# ersa_schematics_digital.net
KiCad netlist of a schematic drawn in Altium Designer
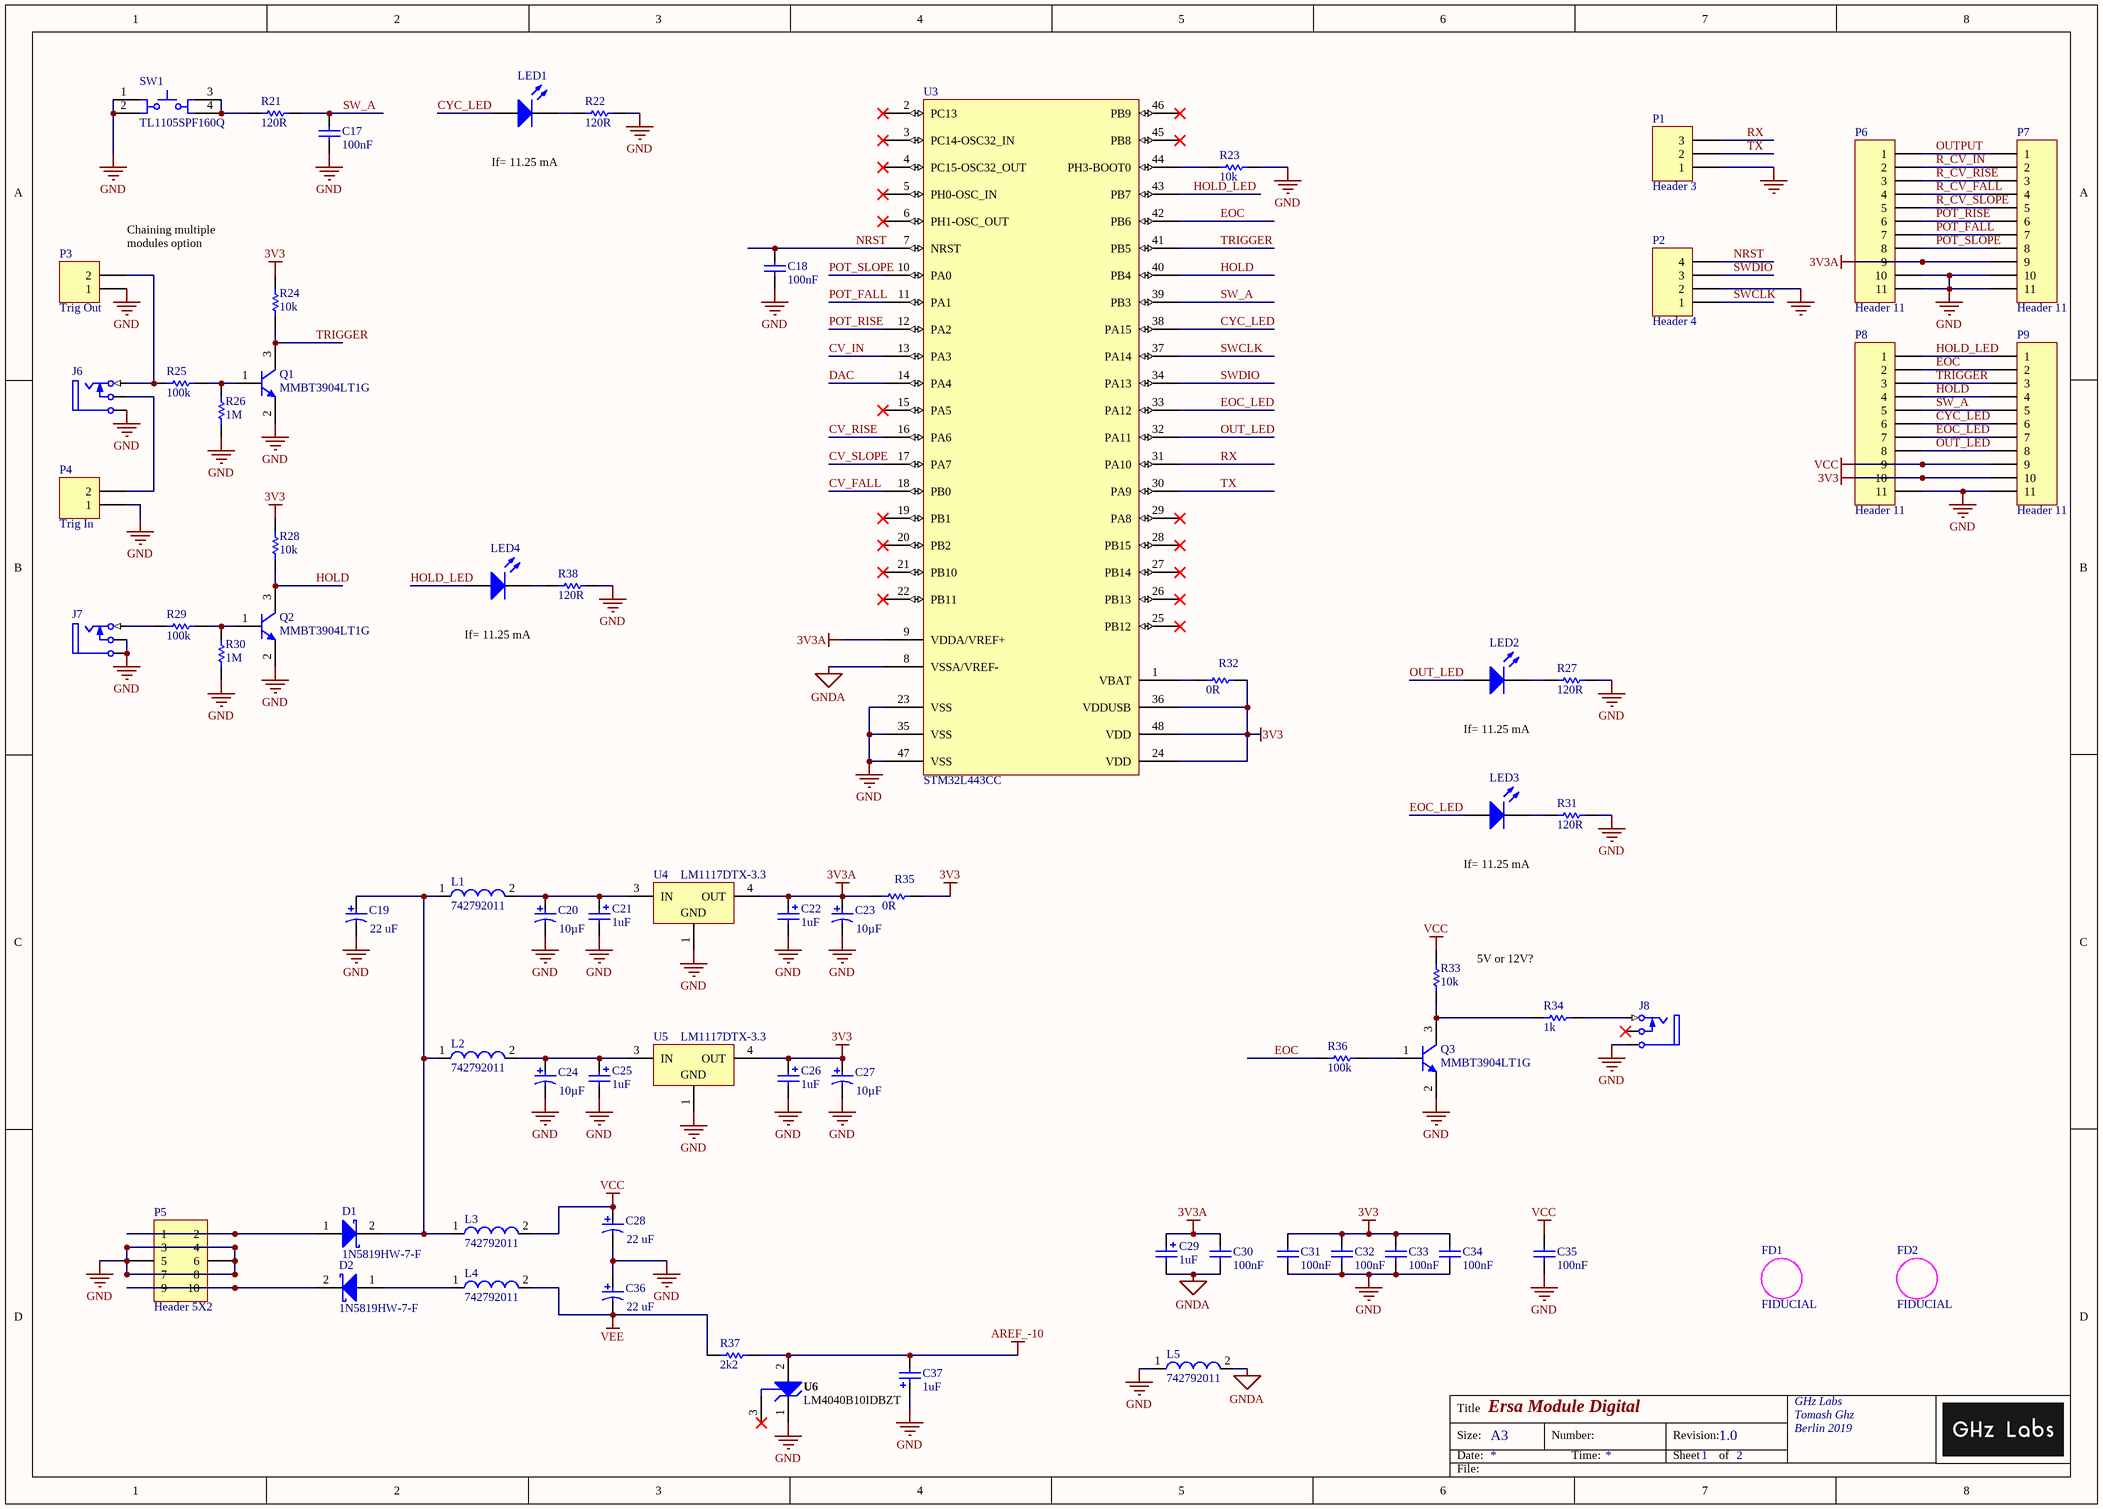
[diagram p0: ersa_schematics_digital.SchDoc]

(export (version "E")
  (design (tool "Eeschema 10.0.6"))
  (components
    (comp (ref "C17")
      (value "100nF")
      (footprint "GHzLabs_Parts:CAPA_0805")
      (description "Capacitor")
      (fields (field (name "PUBLISHER") "Altium Limited"))
      (libsource (lib "Miscellaneous Devices") (part "Cap"))
    )
    (comp (ref "C18")
      (value "100nF")
      (footprint "GHzLabs_Parts:CAPA_0805")
      (description "Capacitor")
      (fields (field (name "PUBLISHER") "Altium Limited"))
      (libsource (lib "Miscellaneous Devices") (part "Cap"))
    )
    (comp (ref "C19")
      (value "UUD1C220MCL1GS")
      (footprint "NIC-CAPA2-5X5.8_V")
      (fields (field (name "RATED CAPACITANCE") "22 uF") (field (name "MANUFACTURER") "Nichicon"))
      (libsource (lib "Altium Content Vault") (part "CMP-0687-00027-1"))
    )
    (comp (ref "C20")
      (value "EEE-FK1V100UR")
      (footprint "PNSC-FK-V-B_V")
      (fields (field (name "MANUFACTURER") "Panasonic") (field (name "CAPACITANCE") "10µF"))
      (libsource (lib "Altium Content Vault") (part "CMP-2000-06211-1"))
    )
    (comp (ref "C21")
      (value "1uF")
      (footprint "GHzLabs_Parts:CAPA_0805 Pol")
      (description "Polarized Capacitor")
      (fields
        (field (name "PARTNUMBER") "GRM21BR61C105KA01L")
        (field (name "MANUFACTURER") "Murata Electronics")
      )
      (libsource (lib "Miscellaneous Devices") (part "Cap Pol2"))
    )
    (comp (ref "C22")
      (value "1uF")
      (footprint "GHzLabs_Parts:CAPA_0805 Pol")
      (description "Polarized Capacitor")
      (fields
        (field (name "PARTNUMBER") "GRM21BR61C105KA01L")
        (field (name "MANUFACTURER") "Murata Electronics")
      )
      (libsource (lib "Miscellaneous Devices") (part "Cap Pol2"))
    )
    (comp (ref "C23")
      (value "EEE-FK1V100UR")
      (footprint "PNSC-FK-V-B_V")
      (fields (field (name "MANUFACTURER") "Panasonic") (field (name "CAPACITANCE") "10µF"))
      (libsource (lib "Altium Content Vault") (part "CMP-2000-06211-1"))
    )
    (comp (ref "C24")
      (value "EEE-FK1V100UR")
      (footprint "PNSC-FK-V-B_V")
      (fields (field (name "MANUFACTURER") "Panasonic") (field (name "CAPACITANCE") "10µF"))
      (libsource (lib "Altium Content Vault") (part "CMP-2000-06211-1"))
    )
    (comp (ref "C25")
      (value "1uF")
      (footprint "GHzLabs_Parts:CAPA_0805 Pol")
      (description "Polarized Capacitor")
      (fields
        (field (name "PARTNUMBER") "GRM21BR61C105KA01L")
        (field (name "MANUFACTURER") "Murata Electronics")
      )
      (libsource (lib "Miscellaneous Devices") (part "Cap Pol2"))
    )
    (comp (ref "C26")
      (value "1uF")
      (footprint "GHzLabs_Parts:CAPA_0805 Pol")
      (description "Polarized Capacitor")
      (fields
        (field (name "PARTNUMBER") "GRM21BR61C105KA01L")
        (field (name "MANUFACTURER") "Murata Electronics")
      )
      (libsource (lib "Miscellaneous Devices") (part "Cap Pol2"))
    )
    (comp (ref "C27")
      (value "EEE-FK1V100UR")
      (footprint "PNSC-FK-V-B_V")
      (fields (field (name "MANUFACTURER") "Panasonic") (field (name "CAPACITANCE") "10µF"))
      (libsource (lib "Altium Content Vault") (part "CMP-2000-06211-1"))
    )
    (comp (ref "C28")
      (value "UUD1C220MCL1GS")
      (footprint "NIC-CAPA2-5X5.8_V")
      (fields (field (name "RATED CAPACITANCE") "22 uF") (field (name "MANUFACTURER") "Nichicon"))
      (libsource (lib "Altium Content Vault") (part "CMP-0687-00027-1"))
    )
    (comp (ref "C29")
      (value "1uF")
      (footprint "GHzLabs_Parts:CAPA_0805 Pol")
      (description "Polarized Capacitor")
      (fields
        (field (name "PARTNUMBER") "GRM21BR61C105KA01L")
        (field (name "MANUFACTURER") "Murata Electronics")
      )
      (libsource (lib "Miscellaneous Devices") (part "Cap Pol2"))
    )
    (comp (ref "C30")
      (value "100nF")
      (footprint "GHzLabs_Parts:CAPA_0805")
      (description "Capacitor")
      (fields (field (name "PUBLISHER") "Altium Limited"))
      (libsource (lib "Miscellaneous Devices") (part "Cap"))
    )
    (comp (ref "C31")
      (value "100nF")
      (footprint "GHzLabs_Parts:CAPA_0805")
      (description "Capacitor")
      (fields (field (name "PUBLISHER") "Altium Limited"))
      (libsource (lib "Miscellaneous Devices") (part "Cap"))
    )
    (comp (ref "C32")
      (value "100nF")
      (footprint "GHzLabs_Parts:CAPA_0805")
      (description "Capacitor")
      (fields (field (name "PUBLISHER") "Altium Limited"))
      (libsource (lib "Miscellaneous Devices") (part "Cap"))
    )
    (comp (ref "C33")
      (value "100nF")
      (footprint "GHzLabs_Parts:CAPA_0805")
      (description "Capacitor")
      (fields (field (name "PUBLISHER") "Altium Limited"))
      (libsource (lib "Miscellaneous Devices") (part "Cap"))
    )
    (comp (ref "C34")
      (value "100nF")
      (footprint "GHzLabs_Parts:CAPA_0805")
      (description "Capacitor")
      (fields (field (name "PUBLISHER") "Altium Limited"))
      (libsource (lib "Miscellaneous Devices") (part "Cap"))
    )
    (comp (ref "C35")
      (value "100nF")
      (footprint "GHzLabs_Parts:CAPA_0805")
      (description "Capacitor")
      (fields (field (name "PUBLISHER") "Altium Limited"))
      (libsource (lib "Miscellaneous Devices") (part "Cap"))
    )
    (comp (ref "C36")
      (value "UUD1C220MCL1GS")
      (footprint "NIC-CAPA2-5X5.8_V")
      (fields (field (name "RATED CAPACITANCE") "22 uF") (field (name "MANUFACTURER") "Nichicon"))
      (libsource (lib "Altium Content Vault") (part "CMP-0687-00027-1"))
    )
    (comp (ref "C37")
      (value "1uF")
      (footprint "GHzLabs_Parts:CAPA_0805 Pol")
      (description "Polarized Capacitor")
      (fields
        (field (name "PARTNUMBER") "GRM21BR61C105KA01L")
        (field (name "MANUFACTURER") "Murata Electronics")
      )
      (libsource (lib "Miscellaneous Devices") (part "Cap Pol2"))
    )
    (comp (ref "D1")
      (value "1N5819HW-7-F")
      (footprint "DIOD-SOD-123-2_V")
      (fields (field (name "MANUFACTURER") "Diodes Inc"))
      (libsource (lib "Altium Content Vault") (part "DIOD-DSKY-A1K2-2"))
    )
    (comp (ref "D2")
      (value "1N5819HW-7-F")
      (footprint "DIOD-SOD-123-2_V")
      (fields (field (name "MANUFACTURER") "Diodes Inc"))
      (libsource (lib "Altium Content Vault") (part "DIOD-DSKY-A1K2-2"))
    )
    (comp (ref "FD1")
      (value "FIDUCIAL")
      (footprint "GHzLabs_Parts:FIDUCIAL")
      (description "Fiducial - Round 1.5 mm Top-Bottom")
      (fields (field (name "MANUFACTURER") "No Vendor"))
      (libsource (lib "GHzLabs_Parts") (part "FIDUCIAL_ROUND"))
    )
    (comp (ref "FD2")
      (value "FIDUCIAL")
      (footprint "GHzLabs_Parts:FIDUCIAL")
      (description "Fiducial - Round 1.5 mm Top-Bottom")
      (fields (field (name "MANUFACTURER") "No Vendor"))
      (libsource (lib "GHzLabs_Parts") (part "FIDUCIAL_ROUND"))
    )
    (comp (ref "J6")
      (value "Phonejack2 TN")
      (footprint "GHzLabs_Parts:Thonkiconn")
      (description "Jack Socket")
      (fields (field (name "PART") "ACJM-MV35-2S") (field (name "MANUFACTURER") "Amphenol Audio"))
      (libsource (lib "GHzLabs_Parts") (part "Phonejack2 TN"))
    )
    (comp (ref "J7")
      (value "Phonejack2 TN")
      (footprint "GHzLabs_Parts:Thonkiconn")
      (description "Jack Socket")
      (fields (field (name "PART") "ACJM-MV35-2S") (field (name "MANUFACTURER") "Amphenol Audio"))
      (libsource (lib "GHzLabs_Parts") (part "Phonejack2 TN"))
    )
    (comp (ref "J8")
      (value "Phonejack2 TN")
      (footprint "GHzLabs_Parts:Thonkiconn")
      (description "Jack Socket")
      (fields (field (name "PART") "ACJM-MV35-2S") (field (name "MANUFACTURER") "Amphenol Audio"))
      (libsource (lib "GHzLabs_Parts") (part "Phonejack2 TN"))
    )
    (comp (ref "L1")
      (value "742792011")
      (footprint "SMD-0805")
      (description "SMD EMI Suppression Ferrite Bead WE-CBF, Z = 10 Ohm")
      (libsource (lib "Altium Content Vault") (part "PAS-IND-INDUCTOR-2"))
    )
    (comp (ref "L2")
      (value "742792011")
      (footprint "SMD-0805")
      (description "SMD EMI Suppression Ferrite Bead WE-CBF, Z = 10 Ohm")
      (libsource (lib "Altium Content Vault") (part "PAS-IND-INDUCTOR-2"))
    )
    (comp (ref "L3")
      (value "742792011")
      (footprint "SMD-0805")
      (description "SMD EMI Suppression Ferrite Bead WE-CBF, Z = 10 Ohm")
      (libsource (lib "Altium Content Vault") (part "PAS-IND-INDUCTOR-2"))
    )
    (comp (ref "L4")
      (value "742792011")
      (footprint "SMD-0805")
      (description "SMD EMI Suppression Ferrite Bead WE-CBF, Z = 10 Ohm")
      (libsource (lib "Altium Content Vault") (part "PAS-IND-INDUCTOR-2"))
    )
    (comp (ref "L5")
      (value "742792011")
      (footprint "SMD-0805")
      (description "SMD EMI Suppression Ferrite Bead WE-CBF, Z = 10 Ohm")
      (libsource (lib "Altium Content Vault") (part "PAS-IND-INDUCTOR-2"))
    )
    (comp (ref "LED1")
      (value "WP424YDT")
      (footprint "Type 3mm")
      (description "THT LED round mono-color color lens, WL-TMRC, Bright Green")
      (fields (field (name "MANUFACTURER") "Kingbright"))
      (libsource (lib "Altium Content Vault") (part "CMP-1488-00001-1"))
    )
    (comp (ref "LED2")
      (value "WP424YDT")
      (footprint "Type 3mm")
      (description "THT LED round mono-color color lens, WL-TMRC, Bright Green")
      (fields (field (name "MANUFACTURER") "Kingbright"))
      (libsource (lib "Altium Content Vault") (part "CMP-1488-00001-1"))
    )
    (comp (ref "LED3")
      (value "WP424YDT")
      (footprint "Type 3mm")
      (description "THT LED round mono-color color lens, WL-TMRC, Bright Green")
      (fields (field (name "MANUFACTURER") "Kingbright"))
      (libsource (lib "Altium Content Vault") (part "CMP-1488-00001-1"))
    )
    (comp (ref "LED4")
      (value "WP424YDT")
      (footprint "Type 3mm")
      (description "THT LED round mono-color color lens, WL-TMRC, Bright Green")
      (fields (field (name "MANUFACTURER") "Kingbright"))
      (libsource (lib "Altium Content Vault") (part "CMP-1488-00001-1"))
    )
    (comp (ref "P1")
      (value "Header 3")
      (footprint "HDR1X3")
      (description "Header, 3-Pin")
      (fields (field (name "PUBLISHER") "Altium Limited"))
      (libsource (lib "Miscellaneous Connectors") (part "Header 3"))
    )
    (comp (ref "P2")
      (value "Header 4")
      (footprint "HDR1X4")
      (description "Header, 4-Pin")
      (fields (field (name "PUBLISHER") "Altium Limited"))
      (libsource (lib "Miscellaneous Connectors") (part "Header 4"))
    )
    (comp (ref "P3")
      (value "Trig Out")
      (footprint "HDR1X2")
      (description "Header, 2-Pin")
      (fields (field (name "PUBLISHER") "Altium Limited"))
      (libsource (lib "Miscellaneous Connectors") (part "Header 2"))
    )
    (comp (ref "P4")
      (value "Trig In")
      (footprint "HDR1X2")
      (description "Header, 2-Pin")
      (fields (field (name "PUBLISHER") "Altium Limited"))
      (libsource (lib "Miscellaneous Connectors") (part "Header 2"))
    )
    (comp (ref "P5")
      (value "Header 5X2")
      (footprint "HDR2X5")
      (description "Header, 5-Pin, Dual row")
      (fields (field (name "PUBLISHER") "Altium Limited"))
      (libsource (lib "Miscellaneous Connectors") (part "Header 5X2"))
    )
    (comp (ref "P6")
      (value "Header 11")
      (footprint "HDR1X11")
      (description "Header, 11-Pin")
      (fields (field (name "PUBLISHER") "Altium Limited"))
      (libsource (lib "Miscellaneous Connectors") (part "Header 11"))
    )
    (comp (ref "P7")
      (value "Header 11")
      (footprint "HDR1X11")
      (description "Header, 11-Pin")
      (fields (field (name "PUBLISHER") "Altium Limited"))
      (libsource (lib "") (part "Header 11_1"))
    )
    (comp (ref "P8")
      (value "Header 11")
      (footprint "HDR1X11")
      (description "Header, 11-Pin")
      (fields (field (name "PUBLISHER") "Altium Limited"))
      (libsource (lib "Miscellaneous Connectors") (part "Header 11"))
    )
    (comp (ref "P9")
      (value "Header 11")
      (footprint "HDR1X11")
      (description "Header, 11-Pin")
      (fields (field (name "PUBLISHER") "Altium Limited"))
      (libsource (lib "") (part "Header 11_1"))
    )
    (comp (ref "Q1")
      (value "MMBT3904LT1G")
      (footprint "ONSC-SOT-23-3-318-08_V")
      (description "General Purpose Transistor, NPN Silicon, 3-Pin SOT-23, Pb-Free, Tape and Reel")
      (fields (field (name "MANUFACTURER") "On Semiconductor"))
      (libsource (lib "Altium Content Vault") (part "ONSC-NPN-B1E2C3-3"))
    )
    (comp (ref "Q2")
      (value "MMBT3904LT1G")
      (footprint "ONSC-SOT-23-3-318-08_V")
      (description "General Purpose Transistor, NPN Silicon, 3-Pin SOT-23, Pb-Free, Tape and Reel")
      (fields (field (name "MANUFACTURER") "On Semiconductor"))
      (libsource (lib "Altium Content Vault") (part "ONSC-NPN-B1E2C3-3"))
    )
    (comp (ref "Q3")
      (value "MMBT3904LT1G")
      (footprint "ONSC-SOT-23-3-318-08_V")
      (description "General Purpose Transistor, NPN Silicon, 3-Pin SOT-23, Pb-Free, Tape and Reel")
      (fields (field (name "MANUFACTURER") "On Semiconductor"))
      (libsource (lib "Altium Content Vault") (part "ONSC-NPN-B1E2C3-3"))
    )
    (comp (ref "R21")
      (value "120R")
      (footprint "GHzLabs_Parts:RES_0805")
      (description "120R 0805")
      (fields (field (name "PARTNUMBER") "RR1220P-105-D") (field (name "MANUFACTURER") "Susumu"))
      (libsource (lib "GHzLabs_Parts") (part "Resistor"))
    )
    (comp (ref "R22")
      (value "120R")
      (footprint "GHzLabs_Parts:RES_0805")
      (description "120R 0805")
      (fields (field (name "PARTNUMBER") "RR1220P-105-D") (field (name "MANUFACTURER") "Susumu"))
      (libsource (lib "GHzLabs_Parts") (part "Resistor"))
    )
    (comp (ref "R23")
      (value "10k")
      (footprint "GHzLabs_Parts:RES_0805")
      (description "10k 0805")
      (fields (field (name "PARTNUMBER") "RR1220P-105-D") (field (name "MANUFACTURER") "Susumu"))
      (libsource (lib "GHzLabs_Parts") (part "Resistor"))
    )
    (comp (ref "R24")
      (value "10k")
      (footprint "GHzLabs_Parts:RES_0805")
      (description "10k 0805")
      (fields (field (name "PARTNUMBER") "RR1220P-105-D") (field (name "MANUFACTURER") "Susumu"))
      (libsource (lib "GHzLabs_Parts") (part "Resistor"))
    )
    (comp (ref "R25")
      (value "100k")
      (footprint "GHzLabs_Parts:RES_0805")
      (description "100k 0805")
      (fields (field (name "PARTNUMBER") "RR1220P-105-D") (field (name "MANUFACTURER") "Susumu"))
      (libsource (lib "GHzLabs_Parts") (part "Resistor"))
    )
    (comp (ref "R26")
      (value "1M")
      (footprint "GHzLabs_Parts:RES_0805")
      (description "1M 0805")
      (fields (field (name "PARTNUMBER") "RR1220P-105-D") (field (name "MANUFACTURER") "Susumu"))
      (libsource (lib "GHzLabs_Parts") (part "Resistor"))
    )
    (comp (ref "R27")
      (value "120R")
      (footprint "GHzLabs_Parts:RES_0805")
      (description "120R 0805")
      (fields (field (name "PARTNUMBER") "RR1220P-105-D") (field (name "MANUFACTURER") "Susumu"))
      (libsource (lib "GHzLabs_Parts") (part "Resistor"))
    )
    (comp (ref "R28")
      (value "10k")
      (footprint "GHzLabs_Parts:RES_0805")
      (description "10k 0805")
      (fields (field (name "PARTNUMBER") "RR1220P-105-D") (field (name "MANUFACTURER") "Susumu"))
      (libsource (lib "GHzLabs_Parts") (part "Resistor"))
    )
    (comp (ref "R29")
      (value "100k")
      (footprint "GHzLabs_Parts:RES_0805")
      (description "100k 0805")
      (fields (field (name "PARTNUMBER") "RR1220P-105-D") (field (name "MANUFACTURER") "Susumu"))
      (libsource (lib "GHzLabs_Parts") (part "Resistor"))
    )
    (comp (ref "R30")
      (value "1M")
      (footprint "GHzLabs_Parts:RES_0805")
      (description "1M 0805")
      (fields (field (name "PARTNUMBER") "RR1220P-105-D") (field (name "MANUFACTURER") "Susumu"))
      (libsource (lib "GHzLabs_Parts") (part "Resistor"))
    )
    (comp (ref "R31")
      (value "120R")
      (footprint "GHzLabs_Parts:RES_0805")
      (description "120R 0805")
      (fields (field (name "PARTNUMBER") "RR1220P-105-D") (field (name "MANUFACTURER") "Susumu"))
      (libsource (lib "GHzLabs_Parts") (part "Resistor"))
    )
    (comp (ref "R32")
      (value "0R")
      (footprint "GHzLabs_Parts:RES_0805")
      (description "0R 0805")
      (fields (field (name "PARTNUMBER") "RR1220P-104-D") (field (name "MANUFACTURER") "Susumu"))
      (libsource (lib "myParts") (part "Resistor"))
    )
    (comp (ref "R33")
      (value "10k")
      (footprint "GHzLabs_Parts:RES_0805")
      (description "10k 0805")
      (fields (field (name "PARTNUMBER") "RR1220P-105-D") (field (name "MANUFACTURER") "Susumu"))
      (libsource (lib "GHzLabs_Parts") (part "Resistor"))
    )
    (comp (ref "R34")
      (value "1k")
      (footprint "GHzLabs_Parts:RES_0805")
      (description "1k 0805")
      (fields (field (name "PARTNUMBER") "RR1220P-105-D") (field (name "MANUFACTURER") "Susumu"))
      (libsource (lib "GHzLabs_Parts") (part "Resistor"))
    )
    (comp (ref "R35")
      (value "0R")
      (footprint "GHzLabs_Parts:RES_0805")
      (description "0R 0805")
      (fields (field (name "PARTNUMBER") "RR1220P-104-D") (field (name "MANUFACTURER") "Susumu"))
      (libsource (lib "myParts") (part "Resistor"))
    )
    (comp (ref "R36")
      (value "100k")
      (footprint "GHzLabs_Parts:RES_0805")
      (description "100k 0805")
      (fields (field (name "PARTNUMBER") "RR1220P-105-D") (field (name "MANUFACTURER") "Susumu"))
      (libsource (lib "GHzLabs_Parts") (part "Resistor"))
    )
    (comp (ref "R37")
      (value "2k2")
      (footprint "GHzLabs_Parts:RES_0805")
      (description "2k2 0805")
      (fields (field (name "PARTNUMBER") "RR1220P-103-D") (field (name "MANUFACTURER") "Susumu"))
      (libsource (lib "myParts") (part "Resistor"))
    )
    (comp (ref "R38")
      (value "120R")
      (footprint "GHzLabs_Parts:RES_0805")
      (description "120R 0805")
      (fields (field (name "PARTNUMBER") "RR1220P-105-D") (field (name "MANUFACTURER") "Susumu"))
      (libsource (lib "GHzLabs_Parts") (part "Resistor"))
    )
    (comp (ref "SW1")
      (value "TL1105SPF160Q")
      (footprint "ESWI-TL1105SPF_V")
      (description "Tact Switch, SPST-NO, 50 mA, 12 VDC, -20 to 70 degC, 4-Pin THD, RoHS, Bulk")
      (fields (field (name "MANUFACTURER") "E-Switch"))
      (libsource (lib "Altium Content Vault") (part "SW-SPST-NO-4"))
    )
    (comp (ref "U3")
      (value "STM32L443CC")
      (footprint "GHzLabs_Parts:LQFP48 - STM32L443CC")
      (description "STM32L443CC - Ultra-low-power Arm® Cortex®-M4 32-bit MCU+FPU, 100DMIPS, 256KB Flash, 64KB RAM")
      (fields (field (name "PARTNUMBER") "STM32L443CCTx") (field (name "MANUFACTURER") "STMicroelectronics"))
      (libsource (lib "GHzLabs_Parts") (part "STM32L443CC"))
    )
    (comp (ref "U4")
      (value "LM1117DTX-3.3")
      (footprint "TD03B_M")
      (description "800mA Low-Dropout Linear Regulator, 3-pin TO-252")
      (fields (field (name "MANUFACTURER") "National Semiconductor"))
      (libsource (lib "Altium Content Vault") (part "CMP-0062-00706-2"))
    )
    (comp (ref "U5")
      (value "LM1117DTX-3.3")
      (footprint "TD03B_M")
      (description "800mA Low-Dropout Linear Regulator, 3-pin TO-252")
      (fields (field (name "MANUFACTURER") "National Semiconductor"))
      (libsource (lib "Altium Content Vault") (part "CMP-0062-00706-2"))
    )
    (comp (ref "U6")
      (value "LM4040B10IDBZT")
      (footprint "DBZ0003A_M")
      (fields (field (name "MANUFACTURER") "Texas Instruments"))
      (libsource (lib "Altium Content Vault") (part "CMP-0366-01043-2"))
    )
  )
  (nets
    (net (code "1") (name "/CV_FALL") (class "Default")
      (node (ref "U3") (pin "18") (pinfunction "PB0_18") (pintype "bidirectional"))
    )
    (net (code "2") (name "/CV_IN") (class "Default")
      (node (ref "U3") (pin "13") (pinfunction "PA3_13") (pintype "bidirectional"))
    )
    (net (code "3") (name "/CV_RISE") (class "Default")
      (node (ref "U3") (pin "16") (pinfunction "PA6_16") (pintype "bidirectional"))
    )
    (net (code "4") (name "/CV_SLOPE") (class "Default")
      (node (ref "U3") (pin "17") (pinfunction "PA7_17") (pintype "bidirectional"))
    )
    (net (code "5") (name "/CYC_LED") (class "Default")
      (node (ref "LED1") (pin "2") (pinfunction "A_2") (pintype "passive"))
      (node (ref "P8") (pin "6") (pinfunction "6_6") (pintype "passive"))
      (node (ref "P9") (pin "6") (pinfunction "6_6") (pintype "passive"))
      (node (ref "U3") (pin "38") (pinfunction "PA15_38") (pintype "bidirectional"))
    )
    (net (code "6") (name "/DAC") (class "Default")
      (node (ref "U3") (pin "14") (pinfunction "PA4_14") (pintype "bidirectional"))
    )
    (net (code "7") (name "/EOC") (class "Default")
      (node (ref "P8") (pin "2") (pinfunction "2_2") (pintype "passive"))
      (node (ref "P9") (pin "2") (pinfunction "2_2") (pintype "passive"))
      (node (ref "R36") (pin "2") (pinfunction "2_2") (pintype "passive"))
      (node (ref "U3") (pin "42") (pinfunction "PB6_42") (pintype "bidirectional"))
    )
    (net (code "8") (name "/EOC_LED") (class "Default")
      (node (ref "LED3") (pin "2") (pinfunction "A_2") (pintype "passive"))
      (node (ref "P8") (pin "7") (pinfunction "7_7") (pintype "passive"))
      (node (ref "P9") (pin "7") (pinfunction "7_7") (pintype "passive"))
      (node (ref "U3") (pin "33") (pinfunction "PA12_33") (pintype "bidirectional"))
    )
    (net (code "9") (name "/HOLD") (class "Default")
      (node (ref "P8") (pin "4") (pinfunction "4_4") (pintype "passive"))
      (node (ref "P9") (pin "4") (pinfunction "4_4") (pintype "passive"))
      (node (ref "Q2") (pin "3") (pinfunction "C_3") (pintype "passive"))
      (node (ref "R28") (pin "2") (pinfunction "2_2") (pintype "passive"))
      (node (ref "U3") (pin "40") (pinfunction "PB4_40") (pintype "bidirectional"))
    )
    (net (code "10") (name "/HOLD_LED") (class "Default")
      (node (ref "LED4") (pin "2") (pinfunction "A_2") (pintype "passive"))
      (node (ref "P8") (pin "1") (pinfunction "1_1") (pintype "passive"))
      (node (ref "P9") (pin "1") (pinfunction "1_1") (pintype "passive"))
      (node (ref "U3") (pin "43") (pinfunction "PB7_43") (pintype "bidirectional"))
    )
    (net (code "11") (name "/NRST") (class "Default")
      (node (ref "C18") (pin "1") (pinfunction "1_1") (pintype "passive"))
      (node (ref "P2") (pin "4") (pinfunction "4_4") (pintype "passive"))
      (node (ref "U3") (pin "7") (pinfunction "NRST_7") (pintype "bidirectional"))
    )
    (net (code "12") (name "/OUTPUT") (class "Default")
      (node (ref "P6") (pin "1") (pinfunction "1_1") (pintype "passive"))
      (node (ref "P7") (pin "1") (pinfunction "1_1") (pintype "passive"))
    )
    (net (code "13") (name "/OUT_LED") (class "Default")
      (node (ref "LED2") (pin "2") (pinfunction "A_2") (pintype "passive"))
      (node (ref "P8") (pin "8") (pinfunction "8_8") (pintype "passive"))
      (node (ref "P9") (pin "8") (pinfunction "8_8") (pintype "passive"))
      (node (ref "U3") (pin "32") (pinfunction "PA11_32") (pintype "bidirectional"))
    )
    (net (code "14") (name "/POT_FALL") (class "Default")
      (node (ref "P6") (pin "7") (pinfunction "7_7") (pintype "passive"))
      (node (ref "P7") (pin "7") (pinfunction "7_7") (pintype "passive"))
      (node (ref "U3") (pin "11") (pinfunction "PA1_11") (pintype "bidirectional"))
    )
    (net (code "15") (name "/POT_RISE") (class "Default")
      (node (ref "P6") (pin "6") (pinfunction "6_6") (pintype "passive"))
      (node (ref "P7") (pin "6") (pinfunction "6_6") (pintype "passive"))
      (node (ref "U3") (pin "12") (pinfunction "PA2_12") (pintype "bidirectional"))
    )
    (net (code "16") (name "/POT_SLOPE") (class "Default")
      (node (ref "P6") (pin "8") (pinfunction "8_8") (pintype "passive"))
      (node (ref "P7") (pin "8") (pinfunction "8_8") (pintype "passive"))
      (node (ref "U3") (pin "10") (pinfunction "PA0_10") (pintype "bidirectional"))
    )
    (net (code "17") (name "/RX") (class "Default")
      (node (ref "P1") (pin "3") (pinfunction "3_3") (pintype "passive"))
      (node (ref "U3") (pin "31") (pinfunction "PA10_31") (pintype "bidirectional"))
    )
    (net (code "18") (name "/R_CV_FALL") (class "Default")
      (node (ref "P6") (pin "4") (pinfunction "4_4") (pintype "passive"))
      (node (ref "P7") (pin "4") (pinfunction "4_4") (pintype "passive"))
    )
    (net (code "19") (name "/R_CV_IN") (class "Default")
      (node (ref "P6") (pin "2") (pinfunction "2_2") (pintype "passive"))
      (node (ref "P7") (pin "2") (pinfunction "2_2") (pintype "passive"))
    )
    (net (code "20") (name "/R_CV_RISE") (class "Default")
      (node (ref "P6") (pin "3") (pinfunction "3_3") (pintype "passive"))
      (node (ref "P7") (pin "3") (pinfunction "3_3") (pintype "passive"))
    )
    (net (code "21") (name "/R_CV_SLOPE") (class "Default")
      (node (ref "P6") (pin "5") (pinfunction "5_5") (pintype "passive"))
      (node (ref "P7") (pin "5") (pinfunction "5_5") (pintype "passive"))
    )
    (net (code "22") (name "/SWCLK") (class "Default")
      (node (ref "P2") (pin "1") (pinfunction "1_1") (pintype "passive"))
      (node (ref "U3") (pin "37") (pinfunction "PA14_37") (pintype "bidirectional"))
    )
    (net (code "23") (name "/SWDIO") (class "Default")
      (node (ref "P2") (pin "3") (pinfunction "3_3") (pintype "passive"))
      (node (ref "U3") (pin "34") (pinfunction "PA13_34") (pintype "bidirectional"))
    )
    (net (code "24") (name "/SW_A") (class "Default")
      (node (ref "C17") (pin "1") (pinfunction "1_1") (pintype "passive"))
      (node (ref "P8") (pin "5") (pinfunction "5_5") (pintype "passive"))
      (node (ref "P9") (pin "5") (pinfunction "5_5") (pintype "passive"))
      (node (ref "R21") (pin "1") (pinfunction "1_1") (pintype "passive"))
      (node (ref "U3") (pin "39") (pinfunction "PB3_39") (pintype "bidirectional"))
    )
    (net (code "25") (name "/TRIGGER") (class "Default")
      (node (ref "P8") (pin "3") (pinfunction "3_3") (pintype "passive"))
      (node (ref "P9") (pin "3") (pinfunction "3_3") (pintype "passive"))
      (node (ref "Q1") (pin "3") (pinfunction "C_3") (pintype "passive"))
      (node (ref "R24") (pin "2") (pinfunction "2_2") (pintype "passive"))
      (node (ref "U3") (pin "41") (pinfunction "PB5_41") (pintype "bidirectional"))
    )
    (net (code "26") (name "/TX") (class "Default")
      (node (ref "P1") (pin "2") (pinfunction "2_2") (pintype "passive"))
      (node (ref "U3") (pin "30") (pinfunction "PA9_30") (pintype "bidirectional"))
    )
    (net (code "27") (name "3V3") (class "Default")
      (node (ref "C26") (pin "1") (pinfunction "1_1") (pintype "passive"))
      (node (ref "C27") (pin "1") (pinfunction "1_1") (pintype "passive"))
      (node (ref "C31") (pin "1") (pinfunction "1_1") (pintype "passive"))
      (node (ref "C32") (pin "1") (pinfunction "1_1") (pintype "passive"))
      (node (ref "C33") (pin "1") (pinfunction "1_1") (pintype "passive"))
      (node (ref "C34") (pin "1") (pinfunction "1_1") (pintype "passive"))
      (node (ref "P8") (pin "10") (pinfunction "10_10") (pintype "passive"))
      (node (ref "P9") (pin "10") (pinfunction "10_10") (pintype "passive"))
      (node (ref "R24") (pin "1") (pinfunction "1_1") (pintype "passive"))
      (node (ref "R28") (pin "1") (pinfunction "1_1") (pintype "passive"))
      (node (ref "R32") (pin "2") (pinfunction "2_2") (pintype "passive"))
      (node (ref "R35") (pin "2") (pinfunction "2_2") (pintype "passive"))
      (node (ref "U3") (pin "24") (pinfunction "VDD_24") (pintype "power_in"))
      (node (ref "U3") (pin "36") (pinfunction "VDDUSB_36") (pintype "power_in"))
      (node (ref "U3") (pin "48") (pinfunction "VDD_48") (pintype "power_in"))
      (node (ref "U5") (pin "4") (pinfunction "OUT_4") (pintype "power_in"))
    )
    (net (code "28") (name "3V3A") (class "Default")
      (node (ref "C22") (pin "1") (pinfunction "1_1") (pintype "passive"))
      (node (ref "C23") (pin "1") (pinfunction "1_1") (pintype "passive"))
      (node (ref "C29") (pin "1") (pinfunction "1_1") (pintype "passive"))
      (node (ref "C30") (pin "1") (pinfunction "1_1") (pintype "passive"))
      (node (ref "P6") (pin "9") (pinfunction "9_9") (pintype "passive"))
      (node (ref "P7") (pin "9") (pinfunction "9_9") (pintype "passive"))
      (node (ref "R35") (pin "1") (pinfunction "1_1") (pintype "passive"))
      (node (ref "U3") (pin "9") (pinfunction "VDDA/VREF+_9") (pintype "power_in"))
      (node (ref "U4") (pin "4") (pinfunction "OUT_4") (pintype "power_in"))
    )
    (net (code "29") (name "AREF_-10") (class "Default")
      (node (ref "C37") (pin "2") (pinfunction "2_2") (pintype "passive"))
      (node (ref "R37") (pin "1") (pinfunction "1_1") (pintype "passive"))
      (node (ref "U6") (pin "2") (pinfunction "ANODE_2") (pintype "passive"))
    )
    (net (code "30") (name "GND") (class "Default")
      (node (ref "C17") (pin "2") (pinfunction "2_2") (pintype "passive"))
      (node (ref "C18") (pin "2") (pinfunction "2_2") (pintype "passive"))
      (node (ref "C19") (pin "2") (pinfunction "2_2") (pintype "passive"))
      (node (ref "C20") (pin "2") (pinfunction "2_2") (pintype "passive"))
      (node (ref "C21") (pin "2") (pinfunction "2_2") (pintype "passive"))
      (node (ref "C22") (pin "2") (pinfunction "2_2") (pintype "passive"))
      (node (ref "C23") (pin "2") (pinfunction "2_2") (pintype "passive"))
      (node (ref "C24") (pin "2") (pinfunction "2_2") (pintype "passive"))
      (node (ref "C25") (pin "2") (pinfunction "2_2") (pintype "passive"))
      (node (ref "C26") (pin "2") (pinfunction "2_2") (pintype "passive"))
      (node (ref "C27") (pin "2") (pinfunction "2_2") (pintype "passive"))
      (node (ref "C28") (pin "2") (pinfunction "2_2") (pintype "passive"))
      (node (ref "C31") (pin "2") (pinfunction "2_2") (pintype "passive"))
      (node (ref "C32") (pin "2") (pinfunction "2_2") (pintype "passive"))
      (node (ref "C33") (pin "2") (pinfunction "2_2") (pintype "passive"))
      (node (ref "C34") (pin "2") (pinfunction "2_2") (pintype "passive"))
      (node (ref "C35") (pin "2") (pinfunction "2_2") (pintype "passive"))
      (node (ref "C36") (pin "1") (pinfunction "1_1") (pintype "passive"))
      (node (ref "C37") (pin "1") (pinfunction "1_1") (pintype "passive"))
      (node (ref "J6") (pin "5") (pinfunction "S_5") (pintype "power_in"))
      (node (ref "J7") (pin "2") (pinfunction "TN_2") (pintype "passive"))
      (node (ref "J7") (pin "5") (pinfunction "S_5") (pintype "power_in"))
      (node (ref "J8") (pin "5") (pinfunction "S_5") (pintype "power_in"))
      (node (ref "L5") (pin "1") (pinfunction "1_1") (pintype "passive"))
      (node (ref "P1") (pin "1") (pinfunction "1_1") (pintype "passive"))
      (node (ref "P2") (pin "2") (pinfunction "2_2") (pintype "passive"))
      (node (ref "P3") (pin "1") (pinfunction "1_1") (pintype "passive"))
      (node (ref "P4") (pin "1") (pinfunction "1_1") (pintype "passive"))
      (node (ref "P5") (pin "3") (pinfunction "3_3") (pintype "passive"))
      (node (ref "P5") (pin "4") (pinfunction "4_4") (pintype "passive"))
      (node (ref "P5") (pin "5") (pinfunction "5_5") (pintype "passive"))
      (node (ref "P5") (pin "6") (pinfunction "6_6") (pintype "passive"))
      (node (ref "P5") (pin "7") (pinfunction "7_7") (pintype "passive"))
      (node (ref "P5") (pin "8") (pinfunction "8_8") (pintype "passive"))
      (node (ref "P6") (pin "10") (pinfunction "10_10") (pintype "passive"))
      (node (ref "P6") (pin "11") (pinfunction "11_11") (pintype "passive"))
      (node (ref "P7") (pin "10") (pinfunction "10_10") (pintype "passive"))
      (node (ref "P7") (pin "11") (pinfunction "11_11") (pintype "passive"))
      (node (ref "P8") (pin "11") (pinfunction "11_11") (pintype "passive"))
      (node (ref "P9") (pin "11") (pinfunction "11_11") (pintype "passive"))
      (node (ref "Q1") (pin "2") (pinfunction "E_2") (pintype "passive"))
      (node (ref "Q2") (pin "2") (pinfunction "E_2") (pintype "passive"))
      (node (ref "Q3") (pin "2") (pinfunction "E_2") (pintype "passive"))
      (node (ref "R22") (pin "1") (pinfunction "1_1") (pintype "passive"))
      (node (ref "R23") (pin "2") (pinfunction "2_2") (pintype "passive"))
      (node (ref "R26") (pin "2") (pinfunction "2_2") (pintype "passive"))
      (node (ref "R27") (pin "1") (pinfunction "1_1") (pintype "passive"))
      (node (ref "R30") (pin "2") (pinfunction "2_2") (pintype "passive"))
      (node (ref "R31") (pin "1") (pinfunction "1_1") (pintype "passive"))
      (node (ref "R38") (pin "1") (pinfunction "1_1") (pintype "passive"))
      (node (ref "SW1") (pin "1") (pinfunction "1_1") (pintype "passive"))
      (node (ref "SW1") (pin "2") (pinfunction "2_2") (pintype "passive"))
      (node (ref "U3") (pin "23") (pinfunction "VSS_23") (pintype "power_in"))
      (node (ref "U3") (pin "35") (pinfunction "VSS_35") (pintype "power_in"))
      (node (ref "U3") (pin "47") (pinfunction "VSS_47") (pintype "power_in"))
      (node (ref "U4") (pin "1") (pinfunction "GND_1") (pintype "power_in"))
      (node (ref "U5") (pin "1") (pinfunction "GND_1") (pintype "power_in"))
      (node (ref "U6") (pin "1") (pinfunction "CATHODE_1") (pintype "passive"))
    )
    (net (code "31") (name "GNDA") (class "Default")
      (node (ref "C29") (pin "2") (pinfunction "2_2") (pintype "passive"))
      (node (ref "C30") (pin "2") (pinfunction "2_2") (pintype "passive"))
      (node (ref "L5") (pin "2") (pinfunction "2_2") (pintype "passive"))
      (node (ref "U3") (pin "8") (pinfunction "VSSA/VREF-_8") (pintype "power_in"))
    )
    (net (code "32") (name "Net-(D1-A)") (class "Default")
      (node (ref "D1") (pin "1") (pinfunction "A_1") (pintype "passive"))
      (node (ref "P5") (pin "1") (pinfunction "1_1") (pintype "passive"))
      (node (ref "P5") (pin "2") (pinfunction "2_2") (pintype "passive"))
    )
    (net (code "33") (name "Net-(D1-K)") (class "Default")
      (node (ref "C19") (pin "1") (pinfunction "1_1") (pintype "passive"))
      (node (ref "D1") (pin "2") (pinfunction "K_2") (pintype "passive"))
      (node (ref "L1") (pin "1") (pinfunction "1_1") (pintype "passive"))
      (node (ref "L2") (pin "1") (pinfunction "1_1") (pintype "passive"))
      (node (ref "L3") (pin "1") (pinfunction "1_1") (pintype "passive"))
    )
    (net (code "34") (name "Net-(D2-A)") (class "Default")
      (node (ref "D2") (pin "1") (pinfunction "A_1") (pintype "passive"))
      (node (ref "L4") (pin "1") (pinfunction "1_1") (pintype "passive"))
    )
    (net (code "35") (name "Net-(D2-K)") (class "Default")
      (node (ref "D2") (pin "2") (pinfunction "K_2") (pintype "passive"))
      (node (ref "P5") (pin "10") (pinfunction "10_10") (pintype "passive"))
      (node (ref "P5") (pin "9") (pinfunction "9_9") (pintype "passive"))
    )
    (net (code "36") (name "Net-(J6-T)") (class "Default")
      (node (ref "J6") (pin "1") (pinfunction "T_1") (pintype "input"))
      (node (ref "P3") (pin "2") (pinfunction "2_2") (pintype "passive"))
      (node (ref "R25") (pin "2") (pinfunction "2_2") (pintype "passive"))
    )
    (net (code "37") (name "Net-(J6-TN)") (class "Default")
      (node (ref "J6") (pin "2") (pinfunction "TN_2") (pintype "passive"))
      (node (ref "P4") (pin "2") (pinfunction "2_2") (pintype "passive"))
    )
    (net (code "38") (name "Net-(J7-T)") (class "Default")
      (node (ref "J7") (pin "1") (pinfunction "T_1") (pintype "input"))
      (node (ref "R29") (pin "2") (pinfunction "2_2") (pintype "passive"))
    )
    (net (code "39") (name "Net-(J8-T)") (class "Default")
      (node (ref "J8") (pin "1") (pinfunction "T_1") (pintype "input"))
      (node (ref "R34") (pin "1") (pinfunction "1_1") (pintype "passive"))
    )
    (net (code "40") (name "Net-(LED1-K)") (class "Default")
      (node (ref "LED1") (pin "1") (pinfunction "K_1") (pintype "passive"))
      (node (ref "R22") (pin "2") (pinfunction "2_2") (pintype "passive"))
    )
    (net (code "41") (name "Net-(LED2-K)") (class "Default")
      (node (ref "LED2") (pin "1") (pinfunction "K_1") (pintype "passive"))
      (node (ref "R27") (pin "2") (pinfunction "2_2") (pintype "passive"))
    )
    (net (code "42") (name "Net-(LED3-K)") (class "Default")
      (node (ref "LED3") (pin "1") (pinfunction "K_1") (pintype "passive"))
      (node (ref "R31") (pin "2") (pinfunction "2_2") (pintype "passive"))
    )
    (net (code "43") (name "Net-(LED4-K)") (class "Default")
      (node (ref "LED4") (pin "1") (pinfunction "K_1") (pintype "passive"))
      (node (ref "R38") (pin "2") (pinfunction "2_2") (pintype "passive"))
    )
    (net (code "44") (name "Net-(Q1-B)") (class "Default")
      (node (ref "Q1") (pin "1") (pinfunction "B_1") (pintype "passive"))
      (node (ref "R25") (pin "1") (pinfunction "1_1") (pintype "passive"))
      (node (ref "R26") (pin "1") (pinfunction "1_1") (pintype "passive"))
    )
    (net (code "45") (name "Net-(Q2-B)") (class "Default")
      (node (ref "Q2") (pin "1") (pinfunction "B_1") (pintype "passive"))
      (node (ref "R29") (pin "1") (pinfunction "1_1") (pintype "passive"))
      (node (ref "R30") (pin "1") (pinfunction "1_1") (pintype "passive"))
    )
    (net (code "46") (name "Net-(Q3-B)") (class "Default")
      (node (ref "Q3") (pin "1") (pinfunction "B_1") (pintype "passive"))
      (node (ref "R36") (pin "1") (pinfunction "1_1") (pintype "passive"))
    )
    (net (code "47") (name "Net-(Q3-C)") (class "Default")
      (node (ref "Q3") (pin "3") (pinfunction "C_3") (pintype "passive"))
      (node (ref "R33") (pin "2") (pinfunction "2_2") (pintype "passive"))
      (node (ref "R34") (pin "2") (pinfunction "2_2") (pintype "passive"))
    )
    (net (code "48") (name "Net-(R21-Pad2)") (class "Default")
      (node (ref "R21") (pin "2") (pinfunction "2_2") (pintype "passive"))
      (node (ref "SW1") (pin "3") (pinfunction "3_3") (pintype "passive"))
      (node (ref "SW1") (pin "4") (pinfunction "4_4") (pintype "passive"))
    )
    (net (code "49") (name "Net-(U3-PH3-BOOT0)") (class "Default")
      (node (ref "R23") (pin "1") (pinfunction "1_1") (pintype "passive"))
      (node (ref "U3") (pin "44") (pinfunction "PH3-BOOT0_44") (pintype "bidirectional"))
    )
    (net (code "50") (name "Net-(U3-VBAT)") (class "Default")
      (node (ref "R32") (pin "1") (pinfunction "1_1") (pintype "passive"))
      (node (ref "U3") (pin "1") (pinfunction "VBAT_1") (pintype "power_in"))
    )
    (net (code "51") (name "Net-(U4-IN)") (class "Default")
      (node (ref "C20") (pin "1") (pinfunction "1_1") (pintype "passive"))
      (node (ref "C21") (pin "1") (pinfunction "1_1") (pintype "passive"))
      (node (ref "L1") (pin "2") (pinfunction "2_2") (pintype "passive"))
      (node (ref "U4") (pin "3") (pinfunction "IN_3") (pintype "power_in"))
    )
    (net (code "52") (name "Net-(U5-IN)") (class "Default")
      (node (ref "C24") (pin "1") (pinfunction "1_1") (pintype "passive"))
      (node (ref "C25") (pin "1") (pinfunction "1_1") (pintype "passive"))
      (node (ref "L2") (pin "2") (pinfunction "2_2") (pintype "passive"))
      (node (ref "U5") (pin "3") (pinfunction "IN_3") (pintype "power_in"))
    )
    (net (code "53") (name "VCC") (class "Default")
      (node (ref "C28") (pin "1") (pinfunction "1_1") (pintype "passive"))
      (node (ref "C35") (pin "1") (pinfunction "1_1") (pintype "passive"))
      (node (ref "L3") (pin "2") (pinfunction "2_2") (pintype "passive"))
      (node (ref "P8") (pin "9") (pinfunction "9_9") (pintype "passive"))
      (node (ref "P9") (pin "9") (pinfunction "9_9") (pintype "passive"))
      (node (ref "R33") (pin "1") (pinfunction "1_1") (pintype "passive"))
    )
    (net (code "54") (name "VEE") (class "Default")
      (node (ref "C36") (pin "2") (pinfunction "2_2") (pintype "passive"))
      (node (ref "L4") (pin "2") (pinfunction "2_2") (pintype "passive"))
      (node (ref "R37") (pin "2") (pinfunction "2_2") (pintype "passive"))
    )
    (net (code "55") (name "unconnected-(J8-TN-Pad2)") (class "Default")
      (node (ref "J8") (pin "2") (pinfunction "TN_2") (pintype "passive+no_connect"))
    )
    (net (code "56") (name "unconnected-(U3-PA5-Pad15)") (class "Default")
      (node (ref "U3") (pin "15") (pinfunction "PA5_15") (pintype "bidirectional+no_connect"))
    )
    (net (code "57") (name "unconnected-(U3-PA8-Pad29)") (class "Default")
      (node (ref "U3") (pin "29") (pinfunction "PA8_29") (pintype "bidirectional+no_connect"))
    )
    (net (code "58") (name "unconnected-(U3-PB1-Pad19)") (class "Default")
      (node (ref "U3") (pin "19") (pinfunction "PB1_19") (pintype "bidirectional+no_connect"))
    )
    (net (code "59") (name "unconnected-(U3-PB2-Pad20)") (class "Default")
      (node (ref "U3") (pin "20") (pinfunction "PB2_20") (pintype "bidirectional+no_connect"))
    )
    (net (code "60") (name "unconnected-(U3-PB8-Pad45)") (class "Default")
      (node (ref "U3") (pin "45") (pinfunction "PB8_45") (pintype "bidirectional+no_connect"))
    )
    (net (code "61") (name "unconnected-(U3-PB9-Pad46)") (class "Default")
      (node (ref "U3") (pin "46") (pinfunction "PB9_46") (pintype "bidirectional+no_connect"))
    )
    (net (code "62") (name "unconnected-(U3-PB10-Pad21)") (class "Default")
      (node (ref "U3") (pin "21") (pinfunction "PB10_21") (pintype "bidirectional+no_connect"))
    )
    (net (code "63") (name "unconnected-(U3-PB11-Pad22)") (class "Default")
      (node (ref "U3") (pin "22") (pinfunction "PB11_22") (pintype "bidirectional+no_connect"))
    )
    (net (code "64") (name "unconnected-(U3-PB12-Pad25)") (class "Default")
      (node (ref "U3") (pin "25") (pinfunction "PB12_25") (pintype "bidirectional+no_connect"))
    )
    (net (code "65") (name "unconnected-(U3-PB13-Pad26)") (class "Default")
      (node (ref "U3") (pin "26") (pinfunction "PB13_26") (pintype "bidirectional+no_connect"))
    )
    (net (code "66") (name "unconnected-(U3-PB14-Pad27)") (class "Default")
      (node (ref "U3") (pin "27") (pinfunction "PB14_27") (pintype "bidirectional+no_connect"))
    )
    (net (code "67") (name "unconnected-(U3-PB15-Pad28)") (class "Default")
      (node (ref "U3") (pin "28") (pinfunction "PB15_28") (pintype "bidirectional+no_connect"))
    )
    (net (code "68") (name "unconnected-(U3-PC13-Pad2)") (class "Default")
      (node (ref "U3") (pin "2") (pinfunction "PC13_2") (pintype "bidirectional+no_connect"))
    )
    (net (code "69") (name "unconnected-(U3-PC14-OSC32_IN-Pad3)") (class "Default")
      (node (ref "U3") (pin "3") (pinfunction "PC14-OSC32_IN_3") (pintype "bidirectional+no_connect"))
    )
    (net (code "70") (name "unconnected-(U3-PC15-OSC32_OUT-Pad4)") (class "Default")
      (node (ref "U3") (pin "4") (pinfunction "PC15-OSC32_OUT_4") (pintype "bidirectional+no_connect"))
    )
    (net (code "71") (name "unconnected-(U3-PH0-OSC_IN-Pad5)") (class "Default")
      (node (ref "U3") (pin "5") (pinfunction "PH0-OSC_IN_5") (pintype "bidirectional+no_connect"))
    )
    (net (code "72") (name "unconnected-(U3-PH1-OSC_OUT-Pad6)") (class "Default")
      (node (ref "U3") (pin "6") (pinfunction "PH1-OSC_OUT_6") (pintype "bidirectional+no_connect"))
    )
    (net (code "73") (name "unconnected-(U6-NC-Pad3)") (class "Default")
      (node (ref "U6") (pin "3") (pinfunction "NC_3") (pintype "passive+no_connect"))
    )
  )
)
